# esp8266_hat.net
KiCad netlist of a schematic drawn in Altium Designer
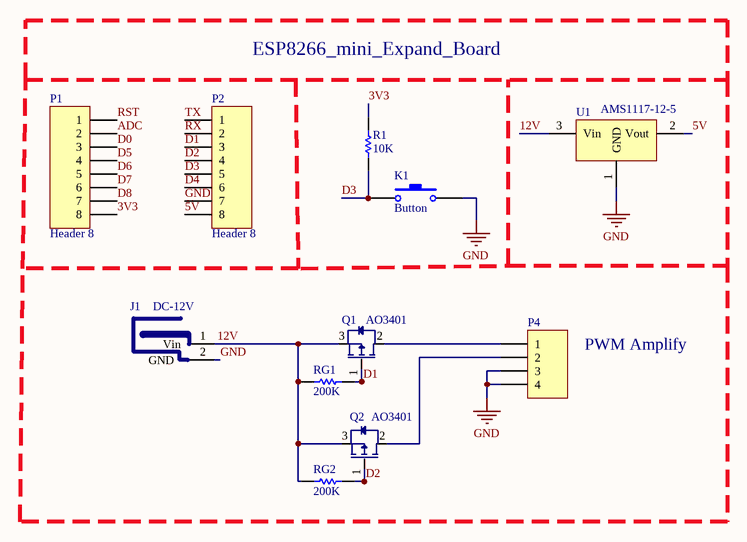
[diagram p0: esp8266_hat.SchDoc]

(export (version "E")
  (design (tool "Eeschema 10.0.6"))
  (components
    (comp (ref "J1")
      (value "DC-12V")
      (footprint "DC-Jack")
      (description "DC-Jack-5.5x2.1mm")
      (libsource (lib "DDTTT") (part "DC-2.5x2.1-005"))
    )
    (comp (ref "K1")
      (value "Button")
      (footprint "KEY_2")
      (description "Switch")
      (fields (field (name "PUBLISHER") "Altium Limited"))
      (libsource (lib "HDU_Wireless") (part "KEY_2"))
    )
    (comp (ref "P1")
      (value "Header 8")
      (footprint "HDR1X8")
      (description "Header, 8-Pin")
      (fields (field (name "PUBLISHER") "Altium Limited"))
      (libsource (lib "") (part "Header 8_1"))
    )
    (comp (ref "P2")
      (value "Header 8")
      (footprint "HDR1X8")
      (description "Header, 8-Pin")
      (fields (field (name "PUBLISHER") "Altium Limited"))
      (libsource (lib "Miscellaneous Connectors") (part "Header 8"))
    )
    (comp (ref "P4")
      (value "Header 4")
      (footprint "HDR1X4")
      (description "Header, 4-Pin")
      (fields (field (name "PUBLISHER") "Altium Limited"))
      (libsource (lib "Miscellaneous Connectors") (part "Header 4"))
    )
    (comp (ref "Q1")
      (value "AO3401")
      (footprint "SOT23")
      (description "PMOS,30V,4A")
      (libsource (lib "DDTTT") (part "AO3401"))
    )
    (comp (ref "Q2")
      (value "AO3401")
      (footprint "SOT23")
      (description "PMOS,30V,4A")
      (libsource (lib "DDTTT") (part "AO3401"))
    )
    (comp (ref "R1")
      (value "10K")
      (footprint "0805_r")
      (description "Resistor")
      (fields (field (name "PUBLISHER") "Altium Limited"))
      (libsource (lib "HDU_Wireless") (part "RES"))
    )
    (comp (ref "RG1")
      (value "200K")
      (footprint "0805_r")
      (description "Resistor")
      (fields (field (name "PUBLISHER") "Altium Limited"))
      (libsource (lib "HDU_Wireless") (part "RES"))
    )
    (comp (ref "RG2")
      (value "200K")
      (footprint "0805_r")
      (description "Resistor")
      (fields (field (name "PUBLISHER") "Altium Limited"))
      (libsource (lib "HDU_Wireless") (part "RES"))
    )
    (comp (ref "U1")
      (value "AMS1117-12-5")
      (footprint "SOT-223")
      (description "3.3V电压转换器AMS1117")
      (libsource (lib "HDU_Wireless") (part "AMS1117"))
    )
  )
  (nets
    (net (code "1") (name "/3V3") (class "Default")
      (node (ref "P1") (pin "8") (pinfunction "8_8") (pintype "passive"))
      (node (ref "R1") (pin "2") (pinfunction "2_2") (pintype "passive"))
    )
    (net (code "2") (name "/5V") (class "Default")
      (node (ref "P2") (pin "8") (pinfunction "8_8") (pintype "passive"))
      (node (ref "U1") (pin "2") (pinfunction "Vout_2") (pintype "passive"))
    )
    (net (code "3") (name "/12V") (class "Default")
      (node (ref "J1") (pin "1") (pinfunction "Vin_1") (pintype "passive"))
      (node (ref "Q1") (pin "3") (pinfunction "S_3") (pintype "passive"))
      (node (ref "Q2") (pin "3") (pinfunction "S_3") (pintype "passive"))
      (node (ref "RG1") (pin "2") (pinfunction "2_2") (pintype "passive"))
      (node (ref "RG2") (pin "2") (pinfunction "2_2") (pintype "passive"))
      (node (ref "U1") (pin "3") (pinfunction "Vin_3") (pintype "passive"))
    )
    (net (code "4") (name "/ADC") (class "Default")
      (node (ref "P1") (pin "2") (pinfunction "2_2") (pintype "passive"))
    )
    (net (code "5") (name "/D0") (class "Default")
      (node (ref "P1") (pin "3") (pinfunction "3_3") (pintype "passive"))
    )
    (net (code "6") (name "/D1") (class "Default")
      (node (ref "P2") (pin "3") (pinfunction "3_3") (pintype "passive"))
      (node (ref "Q1") (pin "1") (pinfunction "G_1") (pintype "passive"))
      (node (ref "RG1") (pin "1") (pinfunction "1_1") (pintype "passive"))
    )
    (net (code "7") (name "/D2") (class "Default")
      (node (ref "P2") (pin "4") (pinfunction "4_4") (pintype "passive"))
      (node (ref "Q2") (pin "1") (pinfunction "G_1") (pintype "passive"))
      (node (ref "RG2") (pin "1") (pinfunction "1_1") (pintype "passive"))
    )
    (net (code "8") (name "/D3") (class "Default")
      (node (ref "K1") (pin "1") (pinfunction "1_1") (pintype "passive"))
      (node (ref "P2") (pin "5") (pinfunction "5_5") (pintype "passive"))
      (node (ref "R1") (pin "1") (pinfunction "1_1") (pintype "passive"))
    )
    (net (code "9") (name "/D4") (class "Default")
      (node (ref "P2") (pin "6") (pinfunction "6_6") (pintype "passive"))
    )
    (net (code "10") (name "/D5") (class "Default")
      (node (ref "P1") (pin "4") (pinfunction "4_4") (pintype "passive"))
    )
    (net (code "11") (name "/D6") (class "Default")
      (node (ref "P1") (pin "5") (pinfunction "5_5") (pintype "passive"))
    )
    (net (code "12") (name "/D7") (class "Default")
      (node (ref "P1") (pin "6") (pinfunction "6_6") (pintype "passive"))
    )
    (net (code "13") (name "/D8") (class "Default")
      (node (ref "P1") (pin "7") (pinfunction "7_7") (pintype "passive"))
    )
    (net (code "14") (name "/RST") (class "Default")
      (node (ref "P1") (pin "1") (pinfunction "1_1") (pintype "passive"))
    )
    (net (code "15") (name "/RX") (class "Default")
      (node (ref "P2") (pin "2") (pinfunction "2_2") (pintype "passive"))
    )
    (net (code "16") (name "/TX") (class "Default")
      (node (ref "P2") (pin "1") (pinfunction "1_1") (pintype "passive"))
    )
    (net (code "17") (name "GND") (class "Default")
      (node (ref "J1") (pin "2") (pinfunction "GND_2") (pintype "passive"))
      (node (ref "K1") (pin "2") (pinfunction "2_2") (pintype "passive"))
      (node (ref "P2") (pin "7") (pinfunction "7_7") (pintype "passive"))
      (node (ref "P4") (pin "3") (pinfunction "3_3") (pintype "passive"))
      (node (ref "P4") (pin "4") (pinfunction "4_4") (pintype "passive"))
      (node (ref "U1") (pin "1") (pinfunction "GND_1") (pintype "passive"))
    )
    (net (code "18") (name "Net-(Q1-D)") (class "Default")
      (node (ref "P4") (pin "1") (pinfunction "1_1") (pintype "passive"))
      (node (ref "Q1") (pin "2") (pinfunction "D_2") (pintype "passive"))
    )
    (net (code "19") (name "Net-(Q2-D)") (class "Default")
      (node (ref "P4") (pin "2") (pinfunction "2_2") (pintype "passive"))
      (node (ref "Q2") (pin "2") (pinfunction "D_2") (pintype "passive"))
    )
  )
)
